# untitled.net
KiCad netlist of a schematic drawn in EAGLE
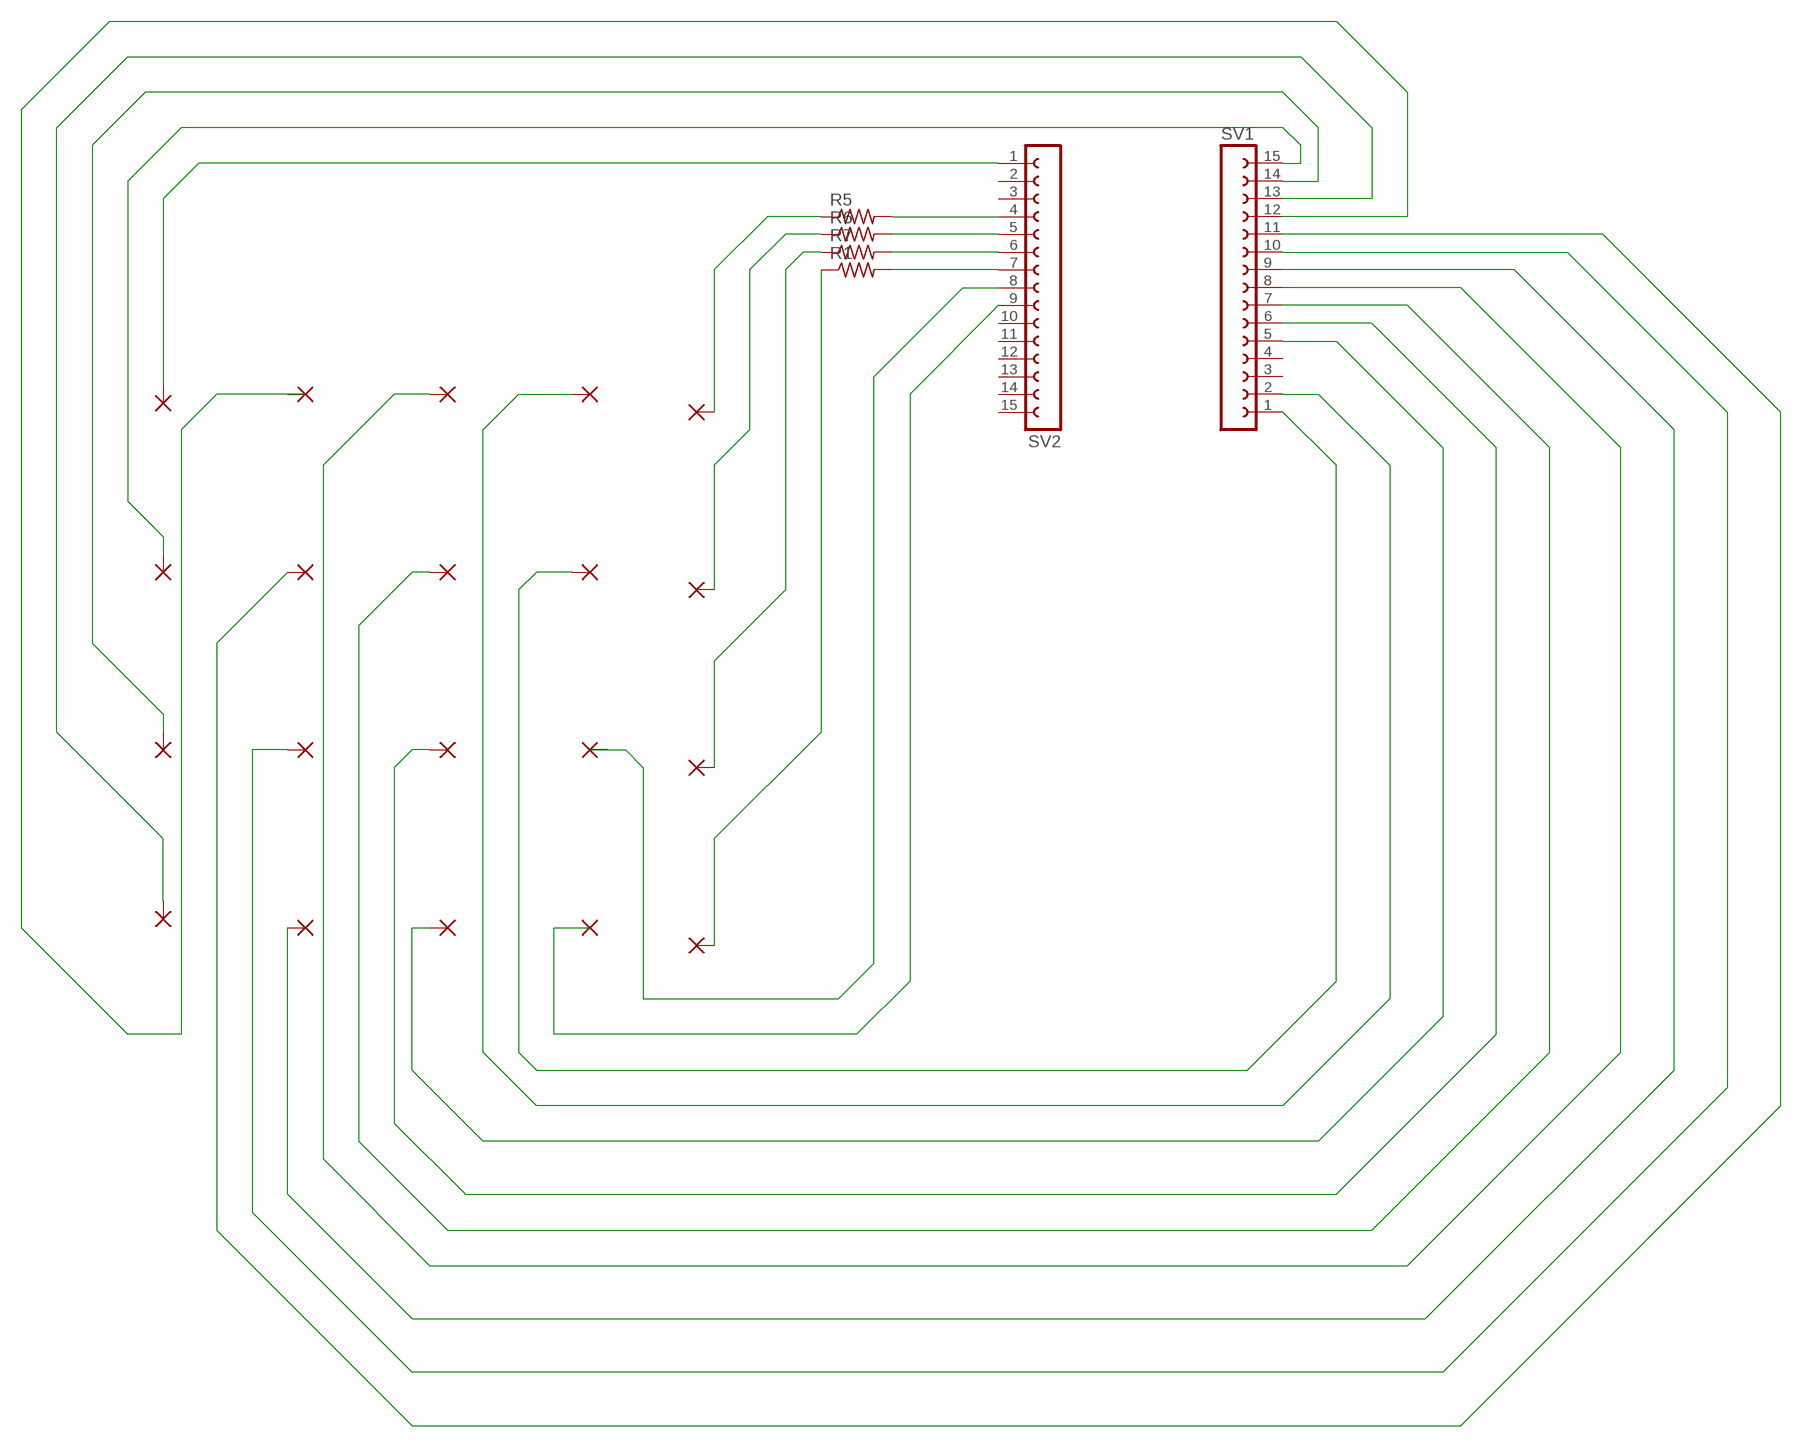
[diagram p0: schematic, sheet 1]

(export (version "E")
  (design (tool "Eeschema 10.0.6"))
  (components
    (comp (ref "PAD1")
      (value "1,6/0,8")
      (footprint "eagle-import:1,6_0,8")
      (libsource (lib "eagle-import") (part "1,6/0,8"))
    )
    (comp (ref "PAD2")
      (value "1,6/0,8")
      (footprint "eagle-import:1,6_0,8")
      (libsource (lib "eagle-import") (part "1,6/0,8"))
    )
    (comp (ref "PAD3")
      (value "1,6/0,8")
      (footprint "eagle-import:1,6_0,8")
      (libsource (lib "eagle-import") (part "1,6/0,8"))
    )
    (comp (ref "PAD4")
      (value "1,6/0,8")
      (footprint "eagle-import:1,6_0,8")
      (libsource (lib "eagle-import") (part "1,6/0,8"))
    )
    (comp (ref "PAD5")
      (value "1,6/0,8")
      (footprint "eagle-import:1,6_0,8")
      (libsource (lib "eagle-import") (part "1,6/0,8"))
    )
    (comp (ref "PAD6")
      (value "1,6/0,8")
      (footprint "eagle-import:1,6_0,8")
      (libsource (lib "eagle-import") (part "1,6/0,8"))
    )
    (comp (ref "PAD7")
      (value "1,6/0,8")
      (footprint "eagle-import:1,6_0,8")
      (libsource (lib "eagle-import") (part "1,6/0,8"))
    )
    (comp (ref "PAD8")
      (value "1,6/0,8")
      (footprint "eagle-import:1,6_0,8")
      (libsource (lib "eagle-import") (part "1,6/0,8"))
    )
    (comp (ref "PAD9")
      (value "1,6/0,8")
      (footprint "eagle-import:1,6_0,8")
      (libsource (lib "eagle-import") (part "1,6/0,8"))
    )
    (comp (ref "PAD10")
      (value "1,6/0,8")
      (footprint "eagle-import:1,6_0,8")
      (libsource (lib "eagle-import") (part "1,6/0,8"))
    )
    (comp (ref "PAD11")
      (value "1,6/0,8")
      (footprint "eagle-import:1,6_0,8")
      (libsource (lib "eagle-import") (part "1,6/0,8"))
    )
    (comp (ref "PAD12")
      (value "1,6/0,8")
      (footprint "eagle-import:1,6_0,8")
      (libsource (lib "eagle-import") (part "1,6/0,8"))
    )
    (comp (ref "PAD13")
      (value "1,6/0,8")
      (footprint "eagle-import:1,6_0,8")
      (libsource (lib "eagle-import") (part "1,6/0,8"))
    )
    (comp (ref "PAD14")
      (value "1,6/0,8")
      (footprint "eagle-import:1,6_0,8")
      (libsource (lib "eagle-import") (part "1,6/0,8"))
    )
    (comp (ref "PAD15")
      (value "1,6/0,8")
      (footprint "eagle-import:1,6_0,8")
      (libsource (lib "eagle-import") (part "1,6/0,8"))
    )
    (comp (ref "PAD16")
      (value "1,6/0,8")
      (footprint "eagle-import:1,6_0,8")
      (libsource (lib "eagle-import") (part "1,6/0,8"))
    )
    (comp (ref "PAD17")
      (value "1,6/0,8")
      (footprint "eagle-import:1,6_0,8")
      (libsource (lib "eagle-import") (part "1,6/0,8"))
    )
    (comp (ref "PAD18")
      (value "1,6/0,8")
      (footprint "eagle-import:1,6_0,8")
      (libsource (lib "eagle-import") (part "1,6/0,8"))
    )
    (comp (ref "PAD19")
      (value "1,6/0,8")
      (footprint "eagle-import:1,6_0,8")
      (libsource (lib "eagle-import") (part "1,6/0,8"))
    )
    (comp (ref "PAD20")
      (value "1,6/0,8")
      (footprint "eagle-import:1,6_0,8")
      (libsource (lib "eagle-import") (part "1,6/0,8"))
    )
    (comp (ref "R1")
      (value "FLIPFLOP-RES")
      (footprint "eagle-import:0805-THM")
      (libsource (lib "eagle-import") (part "FLIPFLOP-RES"))
    )
    (comp (ref "R5")
      (value "FLIPFLOP-RES")
      (footprint "eagle-import:0805-THM")
      (libsource (lib "eagle-import") (part "FLIPFLOP-RES"))
    )
    (comp (ref "R6")
      (value "FLIPFLOP-RES")
      (footprint "eagle-import:0805-THM")
      (libsource (lib "eagle-import") (part "FLIPFLOP-RES"))
    )
    (comp (ref "R7")
      (value "FLIPFLOP-RES")
      (footprint "eagle-import:0805-THM")
      (libsource (lib "eagle-import") (part "FLIPFLOP-RES"))
    )
    (comp (ref "SV1")
      (value "FE15-1")
      (footprint "eagle-import:FE15")
      (libsource (lib "eagle-import") (part "FE15-1"))
    )
    (comp (ref "SV2")
      (value "FE15-1")
      (footprint "eagle-import:FE15")
      (libsource (lib "eagle-import") (part "FE15-1"))
    )
  )
  (nets
    (net (code "1") (name "Net-(PAD1-P)") (class "Default")
      (node (ref "PAD1") (pin "1") (pinfunction "P_1") (pintype "passive"))
      (node (ref "R5") (pin "1") (pinfunction "1_1") (pintype "passive"))
    )
    (net (code "2") (name "Net-(PAD2-P)") (class "Default")
      (node (ref "PAD2") (pin "1") (pinfunction "P_1") (pintype "passive"))
      (node (ref "R6") (pin "1") (pinfunction "1_1") (pintype "passive"))
    )
    (net (code "3") (name "Net-(PAD3-P)") (class "Default")
      (node (ref "PAD3") (pin "1") (pinfunction "P_1") (pintype "passive"))
      (node (ref "R7") (pin "1") (pinfunction "1_1") (pintype "passive"))
    )
    (net (code "4") (name "Net-(PAD4-P)") (class "Default")
      (node (ref "PAD4") (pin "1") (pinfunction "P_1") (pintype "passive"))
      (node (ref "R1") (pin "1") (pinfunction "1_1") (pintype "passive"))
    )
    (net (code "5") (name "Net-(PAD5-P)") (class "Default")
      (node (ref "PAD5") (pin "1") (pinfunction "P_1") (pintype "passive"))
      (node (ref "SV1") (pin "2") (pinfunction "2_2") (pintype "passive"))
    )
    (net (code "6") (name "Net-(PAD6-P)") (class "Default")
      (node (ref "PAD6") (pin "1") (pinfunction "P_1") (pintype "passive"))
      (node (ref "SV1") (pin "1") (pinfunction "1_1") (pintype "passive"))
    )
    (net (code "7") (name "Net-(PAD7-P)") (class "Default")
      (node (ref "PAD7") (pin "1") (pinfunction "P_1") (pintype "passive"))
      (node (ref "SV2") (pin "8") (pinfunction "8_8") (pintype "passive"))
    )
    (net (code "8") (name "Net-(PAD8-P)") (class "Default")
      (node (ref "PAD8") (pin "1") (pinfunction "P_1") (pintype "passive"))
      (node (ref "SV2") (pin "9") (pinfunction "9_9") (pintype "passive"))
    )
    (net (code "9") (name "Net-(PAD9-P)") (class "Default")
      (node (ref "PAD9") (pin "1") (pinfunction "P_1") (pintype "passive"))
      (node (ref "SV1") (pin "8") (pinfunction "8_8") (pintype "passive"))
    )
    (net (code "10") (name "Net-(PAD10-P)") (class "Default")
      (node (ref "PAD10") (pin "1") (pinfunction "P_1") (pintype "passive"))
      (node (ref "SV1") (pin "7") (pinfunction "7_7") (pintype "passive"))
    )
    (net (code "11") (name "Net-(PAD11-P)") (class "Default")
      (node (ref "PAD11") (pin "1") (pinfunction "P_1") (pintype "passive"))
      (node (ref "SV1") (pin "6") (pinfunction "6_6") (pintype "passive"))
    )
    (net (code "12") (name "Net-(PAD12-P)") (class "Default")
      (node (ref "PAD12") (pin "1") (pinfunction "P_1") (pintype "passive"))
      (node (ref "SV1") (pin "5") (pinfunction "5_5") (pintype "passive"))
    )
    (net (code "13") (name "Net-(PAD13-P)") (class "Default")
      (node (ref "PAD13") (pin "1") (pinfunction "P_1") (pintype "passive"))
      (node (ref "SV1") (pin "11") (pinfunction "11_11") (pintype "passive"))
    )
    (net (code "14") (name "Net-(PAD14-P)") (class "Default")
      (node (ref "PAD14") (pin "1") (pinfunction "P_1") (pintype "passive"))
      (node (ref "SV1") (pin "10") (pinfunction "10_10") (pintype "passive"))
    )
    (net (code "15") (name "Net-(PAD15-P)") (class "Default")
      (node (ref "PAD15") (pin "1") (pinfunction "P_1") (pintype "passive"))
      (node (ref "SV1") (pin "9") (pinfunction "9_9") (pintype "passive"))
    )
    (net (code "16") (name "Net-(PAD16-P)") (class "Default")
      (node (ref "PAD16") (pin "1") (pinfunction "P_1") (pintype "passive"))
      (node (ref "SV1") (pin "12") (pinfunction "12_12") (pintype "passive"))
    )
    (net (code "17") (name "Net-(PAD17-P)") (class "Default")
      (node (ref "PAD17") (pin "1") (pinfunction "P_1") (pintype "passive"))
      (node (ref "SV2") (pin "1") (pinfunction "1_1") (pintype "passive"))
    )
    (net (code "18") (name "Net-(PAD18-P)") (class "Default")
      (node (ref "PAD18") (pin "1") (pinfunction "P_1") (pintype "passive"))
      (node (ref "SV1") (pin "15") (pinfunction "15_15") (pintype "passive"))
    )
    (net (code "19") (name "Net-(PAD19-P)") (class "Default")
      (node (ref "PAD19") (pin "1") (pinfunction "P_1") (pintype "passive"))
      (node (ref "SV1") (pin "14") (pinfunction "14_14") (pintype "passive"))
    )
    (net (code "20") (name "Net-(PAD20-P)") (class "Default")
      (node (ref "PAD20") (pin "1") (pinfunction "P_1") (pintype "passive"))
      (node (ref "SV1") (pin "13") (pinfunction "13_13") (pintype "passive"))
    )
    (net (code "21") (name "Net-(R1-Pad2)") (class "Default")
      (node (ref "R1") (pin "2") (pinfunction "2_2") (pintype "passive"))
      (node (ref "SV2") (pin "7") (pinfunction "7_7") (pintype "passive"))
    )
    (net (code "22") (name "Net-(R5-Pad2)") (class "Default")
      (node (ref "R5") (pin "2") (pinfunction "2_2") (pintype "passive"))
      (node (ref "SV2") (pin "4") (pinfunction "4_4") (pintype "passive"))
    )
    (net (code "23") (name "Net-(R6-Pad2)") (class "Default")
      (node (ref "R6") (pin "2") (pinfunction "2_2") (pintype "passive"))
      (node (ref "SV2") (pin "5") (pinfunction "5_5") (pintype "passive"))
    )
    (net (code "24") (name "Net-(R7-Pad2)") (class "Default")
      (node (ref "R7") (pin "2") (pinfunction "2_2") (pintype "passive"))
      (node (ref "SV2") (pin "6") (pinfunction "6_6") (pintype "passive"))
    )
    (net (code "25") (name "unconnected-(SV1-Pad3)") (class "Default")
      (node (ref "SV1") (pin "3") (pinfunction "3_3") (pintype "passive"))
    )
    (net (code "26") (name "unconnected-(SV1-Pad4)") (class "Default")
      (node (ref "SV1") (pin "4") (pinfunction "4_4") (pintype "passive"))
    )
    (net (code "27") (name "unconnected-(SV2-Pad2)") (class "Default")
      (node (ref "SV2") (pin "2") (pinfunction "2_2") (pintype "passive"))
    )
    (net (code "28") (name "unconnected-(SV2-Pad3)") (class "Default")
      (node (ref "SV2") (pin "3") (pinfunction "3_3") (pintype "passive"))
    )
    (net (code "29") (name "unconnected-(SV2-Pad10)") (class "Default")
      (node (ref "SV2") (pin "10") (pinfunction "10_10") (pintype "passive"))
    )
    (net (code "30") (name "unconnected-(SV2-Pad11)") (class "Default")
      (node (ref "SV2") (pin "11") (pinfunction "11_11") (pintype "passive"))
    )
    (net (code "31") (name "unconnected-(SV2-Pad12)") (class "Default")
      (node (ref "SV2") (pin "12") (pinfunction "12_12") (pintype "passive"))
    )
    (net (code "32") (name "unconnected-(SV2-Pad13)") (class "Default")
      (node (ref "SV2") (pin "13") (pinfunction "13_13") (pintype "passive"))
    )
    (net (code "33") (name "unconnected-(SV2-Pad14)") (class "Default")
      (node (ref "SV2") (pin "14") (pinfunction "14_14") (pintype "passive"))
    )
    (net (code "34") (name "unconnected-(SV2-Pad15)") (class "Default")
      (node (ref "SV2") (pin "15") (pinfunction "15_15") (pintype "passive"))
    )
  )
)
